# EBAZ4205__TPS65185.net
KiCad netlist of a schematic drawn in Altium Designer
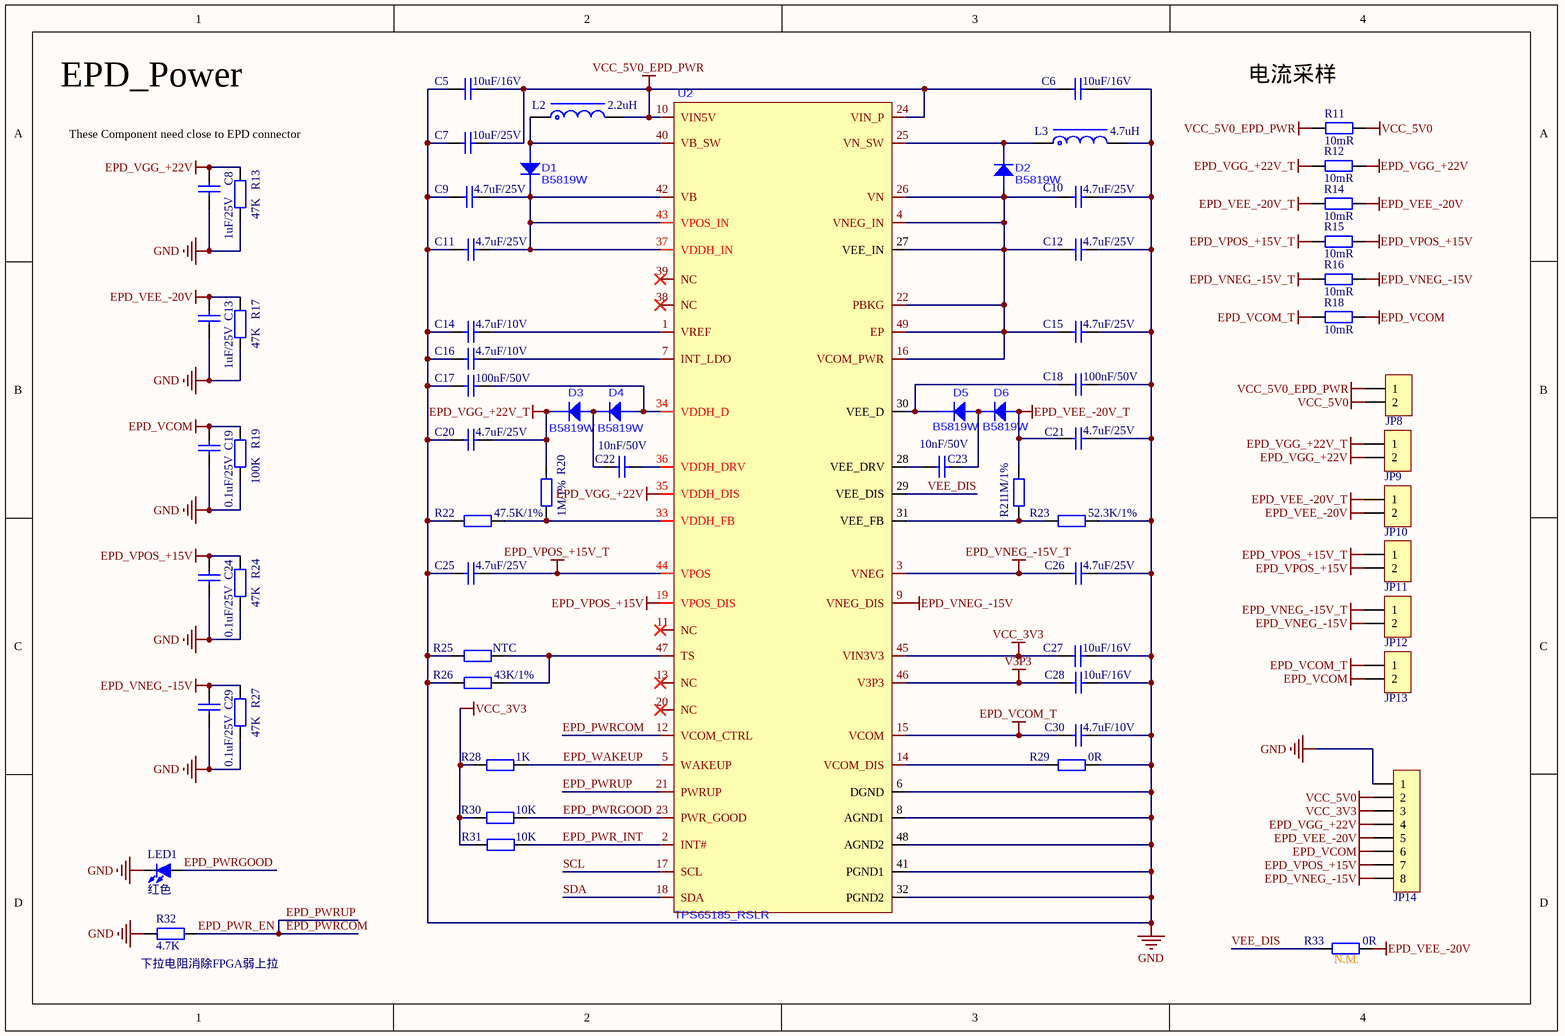
[diagram p0: EBAZ4205扩展_TPS65185.SchDoc]

(export (version "E")
  (design (tool "Eeschema 10.0.6"))
  (components
    (comp (ref "C5")
      (value "10uF/16V")
      (footprint "C0603_L")
      (description "贴片电容")
      (fields (field (name "4.作者声明") "旨为整合最全库集,欢迎转载,禁止商用！-冰凌猫") (field (name "1.库作者") "冰凌猫"))
      (libsource (lib "0.1 - 电阻-电容-电感-磁珠-电位器") (part "C"))
    )
    (comp (ref "C6")
      (value "10uF/16V")
      (footprint "C0603_L")
      (description "贴片电容")
      (fields (field (name "4.作者声明") "旨为整合最全库集,欢迎转载,禁止商用！-冰凌猫") (field (name "1.库作者") "冰凌猫"))
      (libsource (lib "0.1 - 电阻-电容-电感-磁珠-电位器") (part "C"))
    )
    (comp (ref "C7")
      (value "10uF/25V")
      (footprint "C0805_L")
      (description "贴片电容")
      (fields (field (name "4.作者声明") "旨为整合最全库集,欢迎转载,禁止商用！-冰凌猫") (field (name "1.库作者") "冰凌猫"))
      (libsource (lib "0.1 - 电阻-电容-电感-磁珠-电位器") (part "C"))
    )
    (comp (ref "C8")
      (value "1uF/25V")
      (footprint "C0402_L")
      (description "贴片电容")
      (fields (field (name "4.作者声明") "旨为整合最全库集,欢迎转载,禁止商用！-冰凌猫") (field (name "1.库作者") "冰凌猫"))
      (libsource (lib "0.1 - 电阻-电容-电感-磁珠-电位器") (part "C"))
    )
    (comp (ref "C9")
      (value "4.7uF/25V")
      (footprint "C1206_L")
      (description "贴片电容")
      (fields (field (name "4.作者声明") "旨为整合最全库集,欢迎转载,禁止商用！-冰凌猫") (field (name "1.库作者") "冰凌猫"))
      (libsource (lib "0.1 - 电阻-电容-电感-磁珠-电位器") (part "C"))
    )
    (comp (ref "C10")
      (value "4.7uF/25V")
      (footprint "C1206_L")
      (description "贴片电容")
      (fields (field (name "4.作者声明") "旨为整合最全库集,欢迎转载,禁止商用！-冰凌猫") (field (name "1.库作者") "冰凌猫"))
      (libsource (lib "0.1 - 电阻-电容-电感-磁珠-电位器") (part "C"))
    )
    (comp (ref "C11")
      (value "4.7uF/25V")
      (footprint "C1206_L")
      (description "贴片电容")
      (fields (field (name "4.作者声明") "旨为整合最全库集,欢迎转载,禁止商用！-冰凌猫") (field (name "1.库作者") "冰凌猫"))
      (libsource (lib "0.1 - 电阻-电容-电感-磁珠-电位器") (part "C"))
    )
    (comp (ref "C12")
      (value "4.7uF/25V")
      (footprint "C1206_L")
      (description "贴片电容")
      (fields (field (name "4.作者声明") "旨为整合最全库集,欢迎转载,禁止商用！-冰凌猫") (field (name "1.库作者") "冰凌猫"))
      (libsource (lib "0.1 - 电阻-电容-电感-磁珠-电位器") (part "C"))
    )
    (comp (ref "C13")
      (value "1uF/25V")
      (footprint "C0402_L")
      (description "贴片电容")
      (fields (field (name "4.作者声明") "旨为整合最全库集,欢迎转载,禁止商用！-冰凌猫") (field (name "1.库作者") "冰凌猫"))
      (libsource (lib "0.1 - 电阻-电容-电感-磁珠-电位器") (part "C"))
    )
    (comp (ref "C14")
      (value "4.7uF/10V")
      (footprint "C0603_L")
      (description "贴片电容")
      (fields (field (name "4.作者声明") "旨为整合最全库集,欢迎转载,禁止商用！-冰凌猫") (field (name "1.库作者") "冰凌猫"))
      (libsource (lib "0.1 - 电阻-电容-电感-磁珠-电位器") (part "C"))
    )
    (comp (ref "C15")
      (value "4.7uF/25V")
      (footprint "C1206_L")
      (description "贴片电容")
      (fields (field (name "4.作者声明") "旨为整合最全库集,欢迎转载,禁止商用！-冰凌猫") (field (name "1.库作者") "冰凌猫"))
      (libsource (lib "0.1 - 电阻-电容-电感-磁珠-电位器") (part "C"))
    )
    (comp (ref "C16")
      (value "4.7uF/10V")
      (footprint "C0603_L")
      (description "贴片电容")
      (fields (field (name "4.作者声明") "旨为整合最全库集,欢迎转载,禁止商用！-冰凌猫") (field (name "1.库作者") "冰凌猫"))
      (libsource (lib "0.1 - 电阻-电容-电感-磁珠-电位器") (part "C"))
    )
    (comp (ref "C17")
      (value "100nF/50V")
      (footprint "C0603_L")
      (description "贴片电容")
      (fields (field (name "4.作者声明") "旨为整合最全库集,欢迎转载,禁止商用！-冰凌猫") (field (name "1.库作者") "冰凌猫"))
      (libsource (lib "0.1 - 电阻-电容-电感-磁珠-电位器") (part "C"))
    )
    (comp (ref "C18")
      (value "100nF/50V")
      (footprint "C0603_L")
      (description "贴片电容")
      (fields (field (name "4.作者声明") "旨为整合最全库集,欢迎转载,禁止商用！-冰凌猫") (field (name "1.库作者") "冰凌猫"))
      (libsource (lib "0.1 - 电阻-电容-电感-磁珠-电位器") (part "C"))
    )
    (comp (ref "C19")
      (value "0.1uF/25V")
      (footprint "C0402_L")
      (description "贴片电容")
      (fields (field (name "4.作者声明") "旨为整合最全库集,欢迎转载,禁止商用！-冰凌猫") (field (name "1.库作者") "冰凌猫"))
      (libsource (lib "0.1 - 电阻-电容-电感-磁珠-电位器") (part "C"))
    )
    (comp (ref "C20")
      (value "4.7uF/25V")
      (footprint "C1206_L")
      (description "贴片电容")
      (fields (field (name "4.作者声明") "旨为整合最全库集,欢迎转载,禁止商用！-冰凌猫") (field (name "1.库作者") "冰凌猫"))
      (libsource (lib "0.1 - 电阻-电容-电感-磁珠-电位器") (part "C"))
    )
    (comp (ref "C21")
      (value "4.7uF/25V")
      (footprint "C1206_L")
      (description "贴片电容")
      (fields (field (name "4.作者声明") "旨为整合最全库集,欢迎转载,禁止商用！-冰凌猫") (field (name "1.库作者") "冰凌猫"))
      (libsource (lib "0.1 - 电阻-电容-电感-磁珠-电位器") (part "C"))
    )
    (comp (ref "C22")
      (value "10nF/50V")
      (footprint "C0603_L")
      (description "贴片电容")
      (fields (field (name "4.作者声明") "旨为整合最全库集,欢迎转载,禁止商用！-冰凌猫") (field (name "1.库作者") "冰凌猫"))
      (libsource (lib "0.1 - 电阻-电容-电感-磁珠-电位器") (part "C"))
    )
    (comp (ref "C23")
      (value "10nF/50V")
      (footprint "C0603_L")
      (description "贴片电容")
      (fields (field (name "4.作者声明") "旨为整合最全库集,欢迎转载,禁止商用！-冰凌猫") (field (name "1.库作者") "冰凌猫"))
      (libsource (lib "0.1 - 电阻-电容-电感-磁珠-电位器") (part "C"))
    )
    (comp (ref "C24")
      (value "0.1uF/25V")
      (footprint "C0402_L")
      (description "贴片电容")
      (fields (field (name "4.作者声明") "旨为整合最全库集,欢迎转载,禁止商用！-冰凌猫") (field (name "1.库作者") "冰凌猫"))
      (libsource (lib "0.1 - 电阻-电容-电感-磁珠-电位器") (part "C"))
    )
    (comp (ref "C25")
      (value "4.7uF/25V")
      (footprint "C1206_L")
      (description "贴片电容")
      (fields (field (name "4.作者声明") "旨为整合最全库集,欢迎转载,禁止商用！-冰凌猫") (field (name "1.库作者") "冰凌猫"))
      (libsource (lib "0.1 - 电阻-电容-电感-磁珠-电位器") (part "C"))
    )
    (comp (ref "C26")
      (value "4.7uF/25V")
      (footprint "C1206_L")
      (description "贴片电容")
      (fields (field (name "4.作者声明") "旨为整合最全库集,欢迎转载,禁止商用！-冰凌猫") (field (name "1.库作者") "冰凌猫"))
      (libsource (lib "0.1 - 电阻-电容-电感-磁珠-电位器") (part "C"))
    )
    (comp (ref "C27")
      (value "10uF/16V")
      (footprint "C0402_L")
      (description "贴片电容")
      (fields (field (name "4.作者声明") "旨为整合最全库集,欢迎转载,禁止商用！-冰凌猫") (field (name "1.库作者") "冰凌猫"))
      (libsource (lib "0.1 - 电阻-电容-电感-磁珠-电位器") (part "C"))
    )
    (comp (ref "C28")
      (value "10uF/16V")
      (footprint "C0402_L")
      (description "贴片电容")
      (fields (field (name "4.作者声明") "旨为整合最全库集,欢迎转载,禁止商用！-冰凌猫") (field (name "1.库作者") "冰凌猫"))
      (libsource (lib "0.1 - 电阻-电容-电感-磁珠-电位器") (part "C"))
    )
    (comp (ref "C29")
      (value "0.1uF/25V")
      (footprint "C0402_L")
      (description "贴片电容")
      (fields (field (name "4.作者声明") "旨为整合最全库集,欢迎转载,禁止商用！-冰凌猫") (field (name "1.库作者") "冰凌猫"))
      (libsource (lib "0.1 - 电阻-电容-电感-磁珠-电位器") (part "C"))
    )
    (comp (ref "C30")
      (value "4.7uF/10V")
      (footprint "C0603_L")
      (description "贴片电容")
      (fields (field (name "4.作者声明") "旨为整合最全库集,欢迎转载,禁止商用！-冰凌猫") (field (name "1.库作者") "冰凌猫"))
      (libsource (lib "0.1 - 电阻-电容-电感-磁珠-电位器") (part "C"))
    )
    (comp (ref "D1") (value "B5819W") (footprint "SOD-123") (libsource (lib "AD") (part "B5819W")))
    (comp (ref "D2") (value "B5819W") (footprint "SOD-123") (libsource (lib "AD") (part "B5819W")))
    (comp (ref "D3") (value "B5819W") (footprint "SOD-123") (libsource (lib "AD") (part "B5819W")))
    (comp (ref "D4") (value "B5819W") (footprint "SOD-123") (libsource (lib "AD") (part "B5819W")))
    (comp (ref "D5") (value "B5819W") (footprint "SOD-123") (libsource (lib "AD") (part "B5819W")))
    (comp (ref "D6") (value "B5819W") (footprint "SOD-123") (libsource (lib "AD") (part "B5819W")))
    (comp (ref "JP8")
      (value "HDR-1X2")
      (footprint "HDR1.27-LI-2P")
      (description "2P接插件")
      (fields (field (name "版权归属") "源创客"))
      (libsource (lib "4.3   - 接插件-脚距1.27") (part "Header 2"))
    )
    (comp (ref "JP9")
      (value "HDR-1X2")
      (footprint "HDR1.27-LI-2P")
      (description "2P接插件")
      (fields (field (name "版权归属") "源创客"))
      (libsource (lib "4.3   - 接插件-脚距1.27") (part "Header 2"))
    )
    (comp (ref "JP10")
      (value "HDR-1X2")
      (footprint "HDR1.27-LI-2P")
      (description "2P接插件")
      (fields (field (name "版权归属") "源创客"))
      (libsource (lib "4.3   - 接插件-脚距1.27") (part "Header 2"))
    )
    (comp (ref "JP11")
      (value "HDR-1X2")
      (footprint "HDR1.27-LI-2P")
      (description "2P接插件")
      (fields (field (name "版权归属") "源创客"))
      (libsource (lib "4.3   - 接插件-脚距1.27") (part "Header 2"))
    )
    (comp (ref "JP12")
      (value "HDR-1X2")
      (footprint "HDR1.27-LI-2P")
      (description "2P接插件")
      (fields (field (name "版权归属") "源创客"))
      (libsource (lib "4.3   - 接插件-脚距1.27") (part "Header 2"))
    )
    (comp (ref "JP13")
      (value "HDR-1X2")
      (footprint "HDR1.27-LI-2P")
      (description "2P接插件")
      (fields (field (name "版权归属") "源创客"))
      (libsource (lib "4.3   - 接插件-脚距1.27") (part "Header 2"))
    )
    (comp (ref "JP14")
      (value "HDR-1X8")
      (footprint "HDR2.54-LI-8P")
      (description "8P接插件")
      (fields (field (name "版权归属") "源创客"))
      (libsource (lib "4.6   - 接插件-脚距2.54") (part "Header 8"))
    )
    (comp (ref "L2")
      (value "2.2uH")
      (footprint "NR6020")
      (description "太诱-NR磁胶电感")
      (fields (field (name "4.作者声明") "旨为整合最全库集,欢迎转载,禁止商用！-冰凌猫") (field (name "1.库作者") "冰凌猫"))
      (libsource (lib "0.1 - 电阻-电容-电感-磁珠-电位器") (part "L-NR"))
    )
    (comp (ref "L3")
      (value "4.7uH")
      (footprint "NR6020")
      (description "太诱-NR磁胶电感")
      (fields (field (name "4.作者声明") "旨为整合最全库集,欢迎转载,禁止商用！-冰凌猫") (field (name "1.库作者") "冰凌猫"))
      (libsource (lib "0.1 - 电阻-电容-电感-磁珠-电位器") (part "L-NR"))
    )
    (comp (ref "LED1")
      (value "红色")
      (footprint "LED0603_B")
      (description "贴片LED")
      (libsource (lib "0.3 - LED发光二极管") (part "LED-SMD"))
    )
    (comp (ref "R11")
      (value "10mR")
      (footprint "R0805-HP_L")
      (description "贴片精密电阻")
      (libsource (lib "0.1 - 电阻-电容-电感-磁珠-电位器") (part "R-High Precision"))
    )
    (comp (ref "R12")
      (value "10mR")
      (footprint "R0805-HP_L")
      (description "贴片精密电阻")
      (libsource (lib "0.1 - 电阻-电容-电感-磁珠-电位器") (part "R-High Precision"))
    )
    (comp (ref "R13")
      (value "47K")
      (footprint "R0402_L")
      (description "贴片电阻")
      (fields (field (name "4.作者声明") "旨为整合最全库集,欢迎转载,禁止商用！-冰凌猫") (field (name "1.库作者") "冰凌猫"))
      (libsource (lib "0.1 - 电阻-电容-电感-磁珠-电位器") (part "R"))
    )
    (comp (ref "R14")
      (value "10mR")
      (footprint "R0805-HP_L")
      (description "贴片精密电阻")
      (libsource (lib "0.1 - 电阻-电容-电感-磁珠-电位器") (part "R-High Precision"))
    )
    (comp (ref "R15")
      (value "10mR")
      (footprint "R0805-HP_L")
      (description "贴片精密电阻")
      (libsource (lib "0.1 - 电阻-电容-电感-磁珠-电位器") (part "R-High Precision"))
    )
    (comp (ref "R16")
      (value "10mR")
      (footprint "R0805-HP_L")
      (description "贴片精密电阻")
      (libsource (lib "0.1 - 电阻-电容-电感-磁珠-电位器") (part "R-High Precision"))
    )
    (comp (ref "R17")
      (value "47K")
      (footprint "R0402_L")
      (description "贴片电阻")
      (fields (field (name "4.作者声明") "旨为整合最全库集,欢迎转载,禁止商用！-冰凌猫") (field (name "1.库作者") "冰凌猫"))
      (libsource (lib "0.1 - 电阻-电容-电感-磁珠-电位器") (part "R"))
    )
    (comp (ref "R18")
      (value "10mR")
      (footprint "R0805-HP_L")
      (description "贴片精密电阻")
      (libsource (lib "0.1 - 电阻-电容-电感-磁珠-电位器") (part "R-High Precision"))
    )
    (comp (ref "R19")
      (value "100K")
      (footprint "R0402_L")
      (description "贴片电阻")
      (fields (field (name "4.作者声明") "旨为整合最全库集,欢迎转载,禁止商用！-冰凌猫") (field (name "1.库作者") "冰凌猫"))
      (libsource (lib "0.1 - 电阻-电容-电感-磁珠-电位器") (part "R"))
    )
    (comp (ref "R20")
      (value "1M/1%")
      (footprint "R0402_L")
      (description "贴片电阻")
      (fields (field (name "4.作者声明") "旨为整合最全库集,欢迎转载,禁止商用！-冰凌猫") (field (name "1.库作者") "冰凌猫"))
      (libsource (lib "0.1 - 电阻-电容-电感-磁珠-电位器") (part "R"))
    )
    (comp (ref "R21")
      (value "1M/1%")
      (footprint "R0402_L")
      (description "贴片电阻")
      (fields (field (name "4.作者声明") "旨为整合最全库集,欢迎转载,禁止商用！-冰凌猫") (field (name "1.库作者") "冰凌猫"))
      (libsource (lib "0.1 - 电阻-电容-电感-磁珠-电位器") (part "R"))
    )
    (comp (ref "R22")
      (value "47.5K/1%")
      (footprint "R0402_L")
      (description "贴片电阻")
      (fields (field (name "4.作者声明") "旨为整合最全库集,欢迎转载,禁止商用！-冰凌猫") (field (name "1.库作者") "冰凌猫"))
      (libsource (lib "0.1 - 电阻-电容-电感-磁珠-电位器") (part "R"))
    )
    (comp (ref "R23")
      (value "52.3K/1%")
      (footprint "R0402_L")
      (description "贴片电阻")
      (fields (field (name "4.作者声明") "旨为整合最全库集,欢迎转载,禁止商用！-冰凌猫") (field (name "1.库作者") "冰凌猫"))
      (libsource (lib "0.1 - 电阻-电容-电感-磁珠-电位器") (part "R"))
    )
    (comp (ref "R24")
      (value "47K")
      (footprint "R0402_L")
      (description "贴片电阻")
      (fields (field (name "4.作者声明") "旨为整合最全库集,欢迎转载,禁止商用！-冰凌猫") (field (name "1.库作者") "冰凌猫"))
      (libsource (lib "0.1 - 电阻-电容-电感-磁珠-电位器") (part "R"))
    )
    (comp (ref "R25")
      (value "NTC")
      (footprint "R0402_L")
      (description "贴片电阻")
      (fields (field (name "4.作者声明") "旨为整合最全库集,欢迎转载,禁止商用！-冰凌猫") (field (name "1.库作者") "冰凌猫"))
      (libsource (lib "0.1 - 电阻-电容-电感-磁珠-电位器") (part "R"))
    )
    (comp (ref "R26")
      (value "43K/1%")
      (footprint "R0402_L")
      (description "贴片电阻")
      (fields (field (name "4.作者声明") "旨为整合最全库集,欢迎转载,禁止商用！-冰凌猫") (field (name "1.库作者") "冰凌猫"))
      (libsource (lib "0.1 - 电阻-电容-电感-磁珠-电位器") (part "R"))
    )
    (comp (ref "R27")
      (value "47K")
      (footprint "R0402_L")
      (description "贴片电阻")
      (fields (field (name "4.作者声明") "旨为整合最全库集,欢迎转载,禁止商用！-冰凌猫") (field (name "1.库作者") "冰凌猫"))
      (libsource (lib "0.1 - 电阻-电容-电感-磁珠-电位器") (part "R"))
    )
    (comp (ref "R28")
      (value "1K")
      (footprint "R0402_L")
      (description "贴片电阻")
      (fields (field (name "4.作者声明") "旨为整合最全库集,欢迎转载,禁止商用！-冰凌猫") (field (name "1.库作者") "冰凌猫"))
      (libsource (lib "0.1 - 电阻-电容-电感-磁珠-电位器") (part "R"))
    )
    (comp (ref "R29")
      (value "0R")
      (footprint "R0402_L")
      (description "贴片电阻")
      (fields (field (name "4.作者声明") "旨为整合最全库集,欢迎转载,禁止商用！-冰凌猫") (field (name "1.库作者") "冰凌猫"))
      (libsource (lib "0.1 - 电阻-电容-电感-磁珠-电位器") (part "R"))
    )
    (comp (ref "R30")
      (value "10K")
      (footprint "R0402_L")
      (description "贴片电阻")
      (fields (field (name "4.作者声明") "旨为整合最全库集,欢迎转载,禁止商用！-冰凌猫") (field (name "1.库作者") "冰凌猫"))
      (libsource (lib "0.1 - 电阻-电容-电感-磁珠-电位器") (part "R"))
    )
    (comp (ref "R31")
      (value "10K")
      (footprint "R0402_L")
      (description "贴片电阻")
      (fields (field (name "4.作者声明") "旨为整合最全库集,欢迎转载,禁止商用！-冰凌猫") (field (name "1.库作者") "冰凌猫"))
      (libsource (lib "0.1 - 电阻-电容-电感-磁珠-电位器") (part "R"))
    )
    (comp (ref "R32")
      (value "4.7K")
      (footprint "R0402_L")
      (description "贴片电阻")
      (fields (field (name "4.作者声明") "旨为整合最全库集,欢迎转载,禁止商用！-冰凌猫") (field (name "1.库作者") "冰凌猫"))
      (libsource (lib "0.1 - 电阻-电容-电感-磁珠-电位器") (part "R"))
    )
    (comp (ref "R33")
      (value "0R")
      (footprint "R0402_L")
      (description "贴片电阻")
      (fields (field (name "4.作者声明") "旨为整合最全库集,欢迎转载,禁止商用！-冰凌猫") (field (name "1.库作者") "冰凌猫"))
      (libsource (lib "0.1 - 电阻-电容-电感-磁珠-电位器") (part "R"))
    )
    (comp (ref "U2")
      (value "TPS65185_RSLR")
      (footprint "TPS65185_RSLR")
      (libsource (lib "AD") (part "TPS65185_RSLR"))
    )
  )
  (nets
    (net (code "1") (name "/EPD_PWRCOM") (class "Default")
      (node (ref "R32") (pin "1") (pinfunction "1_1") (pintype "passive"))
      (node (ref "U2") (pin "12") (pinfunction "VCOM_CTRL_12") (pintype "passive"))
      (node (ref "U2") (pin "21") (pinfunction "PWRUP_21") (pintype "passive"))
    )
    (net (code "2") (name "/EPD_PWRGOOD") (class "Default")
      (node (ref "LED1") (pin "1") (pinfunction "A_1") (pintype "passive"))
      (node (ref "R30") (pin "1") (pinfunction "1_1") (pintype "passive"))
      (node (ref "U2") (pin "23") (pinfunction "PWR_GOOD_23") (pintype "passive"))
    )
    (net (code "3") (name "/EPD_PWR_INT") (class "Default")
      (node (ref "R31") (pin "1") (pinfunction "1_1") (pintype "passive"))
      (node (ref "U2") (pin "2") (pinfunction "INT#_2") (pintype "passive"))
    )
    (net (code "4") (name "/EPD_WAKEUP") (class "Default")
      (node (ref "R28") (pin "1") (pinfunction "1_1") (pintype "passive"))
      (node (ref "U2") (pin "5") (pinfunction "WAKEUP_5") (pintype "passive"))
    )
    (net (code "5") (name "/SCL") (class "Default")
      (node (ref "U2") (pin "17") (pinfunction "SCL_17") (pintype "passive"))
    )
    (net (code "6") (name "/SDA") (class "Default")
      (node (ref "U2") (pin "18") (pinfunction "SDA_18") (pintype "passive"))
    )
    (net (code "7") (name "/VEE_DIS") (class "Default")
      (node (ref "R33") (pin "1") (pinfunction "1_1") (pintype "passive"))
      (node (ref "U2") (pin "29") (pinfunction "VEE_DIS_29") (pintype "passive"))
    )
    (net (code "8") (name "EPD_VCOM") (class "Default")
      (node (ref "C19") (pin "2") (pinfunction "2_2") (pintype "passive"))
      (node (ref "JP13") (pin "2") (pinfunction "2_2") (pintype "passive"))
      (node (ref "JP14") (pin "6") (pinfunction "6_6") (pintype "passive"))
      (node (ref "R18") (pin "2") (pinfunction "2_2") (pintype "passive"))
      (node (ref "R19") (pin "1") (pinfunction "1_1") (pintype "passive"))
    )
    (net (code "9") (name "EPD_VCOM_T") (class "Default")
      (node (ref "C30") (pin "1") (pinfunction "1_1") (pintype "passive"))
      (node (ref "JP13") (pin "1") (pinfunction "1_1") (pintype "passive"))
      (node (ref "R18") (pin "1") (pinfunction "1_1") (pintype "passive"))
      (node (ref "U2") (pin "15") (pinfunction "VCOM_15") (pintype "passive"))
    )
    (net (code "10") (name "EPD_VEE_-20V") (class "Default")
      (node (ref "C13") (pin "2") (pinfunction "2_2") (pintype "passive"))
      (node (ref "JP10") (pin "2") (pinfunction "2_2") (pintype "passive"))
      (node (ref "JP14") (pin "5") (pinfunction "5_5") (pintype "passive"))
      (node (ref "R14") (pin "2") (pinfunction "2_2") (pintype "passive"))
      (node (ref "R17") (pin "1") (pinfunction "1_1") (pintype "passive"))
      (node (ref "R33") (pin "2") (pinfunction "2_2") (pintype "passive"))
    )
    (net (code "11") (name "EPD_VEE_-20V_T") (class "Default")
      (node (ref "C21") (pin "1") (pinfunction "1_1") (pintype "passive"))
      (node (ref "D6") (pin "1") (pinfunction "A_1") (pintype "passive"))
      (node (ref "JP10") (pin "1") (pinfunction "1_1") (pintype "passive"))
      (node (ref "R14") (pin "1") (pinfunction "1_1") (pintype "passive"))
      (node (ref "R21") (pin "1") (pinfunction "1_1") (pintype "passive"))
    )
    (net (code "12") (name "EPD_VGG_+22V") (class "Default")
      (node (ref "C8") (pin "2") (pinfunction "2_2") (pintype "passive"))
      (node (ref "JP14") (pin "4") (pinfunction "4_4") (pintype "passive"))
      (node (ref "JP9") (pin "2") (pinfunction "2_2") (pintype "passive"))
      (node (ref "R12") (pin "2") (pinfunction "2_2") (pintype "passive"))
      (node (ref "R13") (pin "1") (pinfunction "1_1") (pintype "passive"))
      (node (ref "U2") (pin "35") (pinfunction "VDDH_DIS_35") (pintype "passive"))
    )
    (net (code "13") (name "EPD_VGG_+22V_T") (class "Default")
      (node (ref "C20") (pin "2") (pinfunction "2_2") (pintype "passive"))
      (node (ref "D3") (pin "2") (pinfunction "K_2") (pintype "passive"))
      (node (ref "JP9") (pin "1") (pinfunction "1_1") (pintype "passive"))
      (node (ref "R12") (pin "1") (pinfunction "1_1") (pintype "passive"))
      (node (ref "R20") (pin "1") (pinfunction "1_1") (pintype "passive"))
    )
    (net (code "14") (name "EPD_VNEG_-15V") (class "Default")
      (node (ref "C29") (pin "2") (pinfunction "2_2") (pintype "passive"))
      (node (ref "JP12") (pin "2") (pinfunction "2_2") (pintype "passive"))
      (node (ref "JP14") (pin "8") (pinfunction "8_8") (pintype "passive"))
      (node (ref "R16") (pin "2") (pinfunction "2_2") (pintype "passive"))
      (node (ref "R27") (pin "1") (pinfunction "1_1") (pintype "passive"))
      (node (ref "U2") (pin "9") (pinfunction "VNEG_DIS_9") (pintype "passive"))
    )
    (net (code "15") (name "EPD_VNEG_-15V_T") (class "Default")
      (node (ref "C26") (pin "1") (pinfunction "1_1") (pintype "passive"))
      (node (ref "JP12") (pin "1") (pinfunction "1_1") (pintype "passive"))
      (node (ref "R16") (pin "1") (pinfunction "1_1") (pintype "passive"))
      (node (ref "U2") (pin "3") (pinfunction "VNEG_3") (pintype "passive"))
    )
    (net (code "16") (name "EPD_VPOS_+15V") (class "Default")
      (node (ref "C24") (pin "2") (pinfunction "2_2") (pintype "passive"))
      (node (ref "JP11") (pin "2") (pinfunction "2_2") (pintype "passive"))
      (node (ref "JP14") (pin "7") (pinfunction "7_7") (pintype "passive"))
      (node (ref "R15") (pin "2") (pinfunction "2_2") (pintype "passive"))
      (node (ref "R24") (pin "1") (pinfunction "1_1") (pintype "passive"))
      (node (ref "U2") (pin "19") (pinfunction "VPOS_DIS_19") (pintype "passive"))
    )
    (net (code "17") (name "EPD_VPOS_+15V_T") (class "Default")
      (node (ref "C25") (pin "2") (pinfunction "2_2") (pintype "passive"))
      (node (ref "JP11") (pin "1") (pinfunction "1_1") (pintype "passive"))
      (node (ref "R15") (pin "1") (pinfunction "1_1") (pintype "passive"))
      (node (ref "U2") (pin "44") (pinfunction "VPOS_44") (pintype "passive"))
    )
    (net (code "18") (name "GND") (class "Default")
      (node (ref "C10") (pin "2") (pinfunction "2_2") (pintype "passive"))
      (node (ref "C11") (pin "1") (pinfunction "1_1") (pintype "passive"))
      (node (ref "C12") (pin "2") (pinfunction "2_2") (pintype "passive"))
      (node (ref "C13") (pin "1") (pinfunction "1_1") (pintype "passive"))
      (node (ref "C14") (pin "1") (pinfunction "1_1") (pintype "passive"))
      (node (ref "C15") (pin "2") (pinfunction "2_2") (pintype "passive"))
      (node (ref "C16") (pin "1") (pinfunction "1_1") (pintype "passive"))
      (node (ref "C17") (pin "1") (pinfunction "1_1") (pintype "passive"))
      (node (ref "C18") (pin "2") (pinfunction "2_2") (pintype "passive"))
      (node (ref "C19") (pin "1") (pinfunction "1_1") (pintype "passive"))
      (node (ref "C20") (pin "1") (pinfunction "1_1") (pintype "passive"))
      (node (ref "C21") (pin "2") (pinfunction "2_2") (pintype "passive"))
      (node (ref "C24") (pin "1") (pinfunction "1_1") (pintype "passive"))
      (node (ref "C25") (pin "1") (pinfunction "1_1") (pintype "passive"))
      (node (ref "C26") (pin "2") (pinfunction "2_2") (pintype "passive"))
      (node (ref "C27") (pin "2") (pinfunction "2_2") (pintype "passive"))
      (node (ref "C28") (pin "2") (pinfunction "2_2") (pintype "passive"))
      (node (ref "C29") (pin "1") (pinfunction "1_1") (pintype "passive"))
      (node (ref "C30") (pin "2") (pinfunction "2_2") (pintype "passive"))
      (node (ref "C5") (pin "1") (pinfunction "1_1") (pintype "passive"))
      (node (ref "C6") (pin "2") (pinfunction "2_2") (pintype "passive"))
      (node (ref "C7") (pin "1") (pinfunction "1_1") (pintype "passive"))
      (node (ref "C8") (pin "1") (pinfunction "1_1") (pintype "passive"))
      (node (ref "C9") (pin "1") (pinfunction "1_1") (pintype "passive"))
      (node (ref "JP14") (pin "1") (pinfunction "1_1") (pintype "passive"))
      (node (ref "L3") (pin "2") (pinfunction "2_2") (pintype "passive"))
      (node (ref "LED1") (pin "2") (pinfunction "K_2") (pintype "passive"))
      (node (ref "R13") (pin "2") (pinfunction "2_2") (pintype "passive"))
      (node (ref "R17") (pin "2") (pinfunction "2_2") (pintype "passive"))
      (node (ref "R19") (pin "2") (pinfunction "2_2") (pintype "passive"))
      (node (ref "R22") (pin "2") (pinfunction "2_2") (pintype "passive"))
      (node (ref "R23") (pin "2") (pinfunction "2_2") (pintype "passive"))
      (node (ref "R24") (pin "2") (pinfunction "2_2") (pintype "passive"))
      (node (ref "R25") (pin "2") (pinfunction "2_2") (pintype "passive"))
      (node (ref "R26") (pin "2") (pinfunction "2_2") (pintype "passive"))
      (node (ref "R27") (pin "2") (pinfunction "2_2") (pintype "passive"))
      (node (ref "R29") (pin "2") (pinfunction "2_2") (pintype "passive"))
      (node (ref "R32") (pin "2") (pinfunction "2_2") (pintype "passive"))
      (node (ref "U2") (pin "32") (pinfunction "PGND2_32") (pintype "passive"))
      (node (ref "U2") (pin "41") (pinfunction "PGND1_41") (pintype "passive"))
      (node (ref "U2") (pin "48") (pinfunction "AGND2_48") (pintype "passive"))
      (node (ref "U2") (pin "6") (pinfunction "DGND_6") (pintype "passive"))
      (node (ref "U2") (pin "8") (pinfunction "AGND1_8") (pintype "passive"))
    )
    (net (code "19") (name "Net-(D1-A)") (class "Default")
      (node (ref "D1") (pin "1") (pinfunction "A_1") (pintype "passive"))
      (node (ref "L2") (pin "1") (pinfunction "1_1") (pintype "passive"))
      (node (ref "U2") (pin "40") (pinfunction "VB_SW_40") (pintype "passive"))
    )
    (net (code "20") (name "Net-(D1-K)") (class "Default")
      (node (ref "C11") (pin "2") (pinfunction "2_2") (pintype "passive"))
      (node (ref "C9") (pin "2") (pinfunction "2_2") (pintype "passive"))
      (node (ref "D1") (pin "2") (pinfunction "K_2") (pintype "passive"))
      (node (ref "U2") (pin "37") (pinfunction "VDDH_IN_37") (pintype "passive"))
      (node (ref "U2") (pin "42") (pinfunction "VB_42") (pintype "passive"))
      (node (ref "U2") (pin "43") (pinfunction "VPOS_IN_43") (pintype "passive"))
    )
    (net (code "21") (name "Net-(D2-A)") (class "Default")
      (node (ref "C10") (pin "1") (pinfunction "1_1") (pintype "passive"))
      (node (ref "C12") (pin "1") (pinfunction "1_1") (pintype "passive"))
      (node (ref "C15") (pin "1") (pinfunction "1_1") (pintype "passive"))
      (node (ref "D2") (pin "1") (pinfunction "A_1") (pintype "passive"))
      (node (ref "U2") (pin "16") (pinfunction "VCOM_PWR_16") (pintype "passive"))
      (node (ref "U2") (pin "22") (pinfunction "PBKG_22") (pintype "passive"))
      (node (ref "U2") (pin "26") (pinfunction "VN_26") (pintype "passive"))
      (node (ref "U2") (pin "27") (pinfunction "VEE_IN_27") (pintype "passive"))
      (node (ref "U2") (pin "4") (pinfunction "VNEG_IN_4") (pintype "passive"))
      (node (ref "U2") (pin "49") (pinfunction "EP_49") (pintype "passive"))
    )
    (net (code "22") (name "Net-(D2-K)") (class "Default")
      (node (ref "D2") (pin "2") (pinfunction "K_2") (pintype "passive"))
      (node (ref "L3") (pin "1") (pinfunction "1_1") (pintype "passive"))
      (node (ref "U2") (pin "25") (pinfunction "VN_SW_25") (pintype "passive"))
    )
    (net (code "23") (name "Net-(D3-A)") (class "Default")
      (node (ref "C22") (pin "1") (pinfunction "1_1") (pintype "passive"))
      (node (ref "D3") (pin "1") (pinfunction "A_1") (pintype "passive"))
      (node (ref "D4") (pin "2") (pinfunction "K_2") (pintype "passive"))
    )
    (net (code "24") (name "Net-(D4-A)") (class "Default")
      (node (ref "C17") (pin "2") (pinfunction "2_2") (pintype "passive"))
      (node (ref "D4") (pin "1") (pinfunction "A_1") (pintype "passive"))
      (node (ref "U2") (pin "34") (pinfunction "VDDH_D_34") (pintype "passive"))
    )
    (net (code "25") (name "Net-(D5-A)") (class "Default")
      (node (ref "C23") (pin "2") (pinfunction "2_2") (pintype "passive"))
      (node (ref "D5") (pin "1") (pinfunction "A_1") (pintype "passive"))
      (node (ref "D6") (pin "2") (pinfunction "K_2") (pintype "passive"))
    )
    (net (code "26") (name "Net-(D5-K)") (class "Default")
      (node (ref "C18") (pin "1") (pinfunction "1_1") (pintype "passive"))
      (node (ref "D5") (pin "2") (pinfunction "K_2") (pintype "passive"))
      (node (ref "U2") (pin "30") (pinfunction "VEE_D_30") (pintype "passive"))
    )
    (net (code "27") (name "Net-(U2-INT_LDO)") (class "Default")
      (node (ref "C16") (pin "2") (pinfunction "2_2") (pintype "passive"))
      (node (ref "U2") (pin "7") (pinfunction "INT_LDO_7") (pintype "passive"))
    )
    (net (code "28") (name "Net-(U2-TS)") (class "Default")
      (node (ref "R25") (pin "1") (pinfunction "1_1") (pintype "passive"))
      (node (ref "R26") (pin "1") (pinfunction "1_1") (pintype "passive"))
      (node (ref "U2") (pin "47") (pinfunction "TS_47") (pintype "passive"))
    )
    (net (code "29") (name "Net-(U2-VCOM_DIS)") (class "Default")
      (node (ref "R29") (pin "1") (pinfunction "1_1") (pintype "passive"))
      (node (ref "U2") (pin "14") (pinfunction "VCOM_DIS_14") (pintype "passive"))
    )
    (net (code "30") (name "Net-(U2-VDDH_DRV)") (class "Default")
      (node (ref "C22") (pin "2") (pinfunction "2_2") (pintype "passive"))
      (node (ref "U2") (pin "36") (pinfunction "VDDH_DRV_36") (pintype "passive"))
    )
    (net (code "31") (name "Net-(U2-VDDH_FB)") (class "Default")
      (node (ref "R20") (pin "2") (pinfunction "2_2") (pintype "passive"))
      (node (ref "R22") (pin "1") (pinfunction "1_1") (pintype "passive"))
      (node (ref "U2") (pin "33") (pinfunction "VDDH_FB_33") (pintype "passive"))
    )
    (net (code "32") (name "Net-(U2-VEE_DRV)") (class "Default")
      (node (ref "C23") (pin "1") (pinfunction "1_1") (pintype "passive"))
      (node (ref "U2") (pin "28") (pinfunction "VEE_DRV_28") (pintype "passive"))
    )
    (net (code "33") (name "Net-(U2-VEE_FB)") (class "Default")
      (node (ref "R21") (pin "2") (pinfunction "2_2") (pintype "passive"))
      (node (ref "R23") (pin "1") (pinfunction "1_1") (pintype "passive"))
      (node (ref "U2") (pin "31") (pinfunction "VEE_FB_31") (pintype "passive"))
    )
    (net (code "34") (name "Net-(U2-VREF)") (class "Default")
      (node (ref "C14") (pin "2") (pinfunction "2_2") (pintype "passive"))
      (node (ref "U2") (pin "1") (pinfunction "VREF_1") (pintype "passive"))
    )
    (net (code "35") (name "V3P3") (class "Default")
      (node (ref "C28") (pin "1") (pinfunction "1_1") (pintype "passive"))
      (node (ref "U2") (pin "46") (pinfunction "V3P3_46") (pintype "passive"))
    )
    (net (code "36") (name "VCC_3V3") (class "Default")
      (node (ref "C27") (pin "1") (pinfunction "1_1") (pintype "passive"))
      (node (ref "JP14") (pin "3") (pinfunction "3_3") (pintype "passive"))
      (node (ref "R28") (pin "2") (pinfunction "2_2") (pintype "passive"))
      (node (ref "R30") (pin "2") (pinfunction "2_2") (pintype "passive"))
      (node (ref "R31") (pin "2") (pinfunction "2_2") (pintype "passive"))
      (node (ref "U2") (pin "45") (pinfunction "VIN3V3_45") (pintype "passive"))
    )
    (net (code "37") (name "VCC_5V0") (class "Default")
      (node (ref "JP14") (pin "2") (pinfunction "2_2") (pintype "passive"))
      (node (ref "JP8") (pin "2") (pinfunction "2_2") (pintype "passive"))
      (node (ref "R11") (pin "2") (pinfunction "2_2") (pintype "passive"))
    )
    (net (code "38") (name "VCC_5V0_EPD_PWR") (class "Default")
      (node (ref "C5") (pin "2") (pinfunction "2_2") (pintype "passive"))
      (node (ref "C6") (pin "1") (pinfunction "1_1") (pintype "passive"))
      (node (ref "C7") (pin "2") (pinfunction "2_2") (pintype "passive"))
      (node (ref "JP8") (pin "1") (pinfunction "1_1") (pintype "passive"))
      (node (ref "L2") (pin "2") (pinfunction "2_2") (pintype "passive"))
      (node (ref "R11") (pin "1") (pinfunction "1_1") (pintype "passive"))
      (node (ref "U2") (pin "10") (pinfunction "VIN5V_10") (pintype "passive"))
      (node (ref "U2") (pin "24") (pinfunction "VIN_P_24") (pintype "passive"))
    )
    (net (code "39") (name "unconnected-(U2-NC-Pad11)") (class "Default")
      (node (ref "U2") (pin "11") (pinfunction "NC_11") (pintype "passive+no_connect"))
    )
    (net (code "40") (name "unconnected-(U2-NC-Pad13)") (class "Default")
      (node (ref "U2") (pin "13") (pinfunction "NC_13") (pintype "passive+no_connect"))
    )
    (net (code "41") (name "unconnected-(U2-NC-Pad20)") (class "Default")
      (node (ref "U2") (pin "20") (pinfunction "NC_20") (pintype "passive+no_connect"))
    )
    (net (code "42") (name "unconnected-(U2-NC-Pad38)") (class "Default")
      (node (ref "U2") (pin "38") (pinfunction "NC_38") (pintype "passive+no_connect"))
    )
    (net (code "43") (name "unconnected-(U2-NC-Pad39)") (class "Default")
      (node (ref "U2") (pin "39") (pinfunction "NC_39") (pintype "passive+no_connect"))
    )
  )
)
